# CW340_USERIO_SerialSelections.net
KiCad netlist of a schematic drawn in Altium Designer
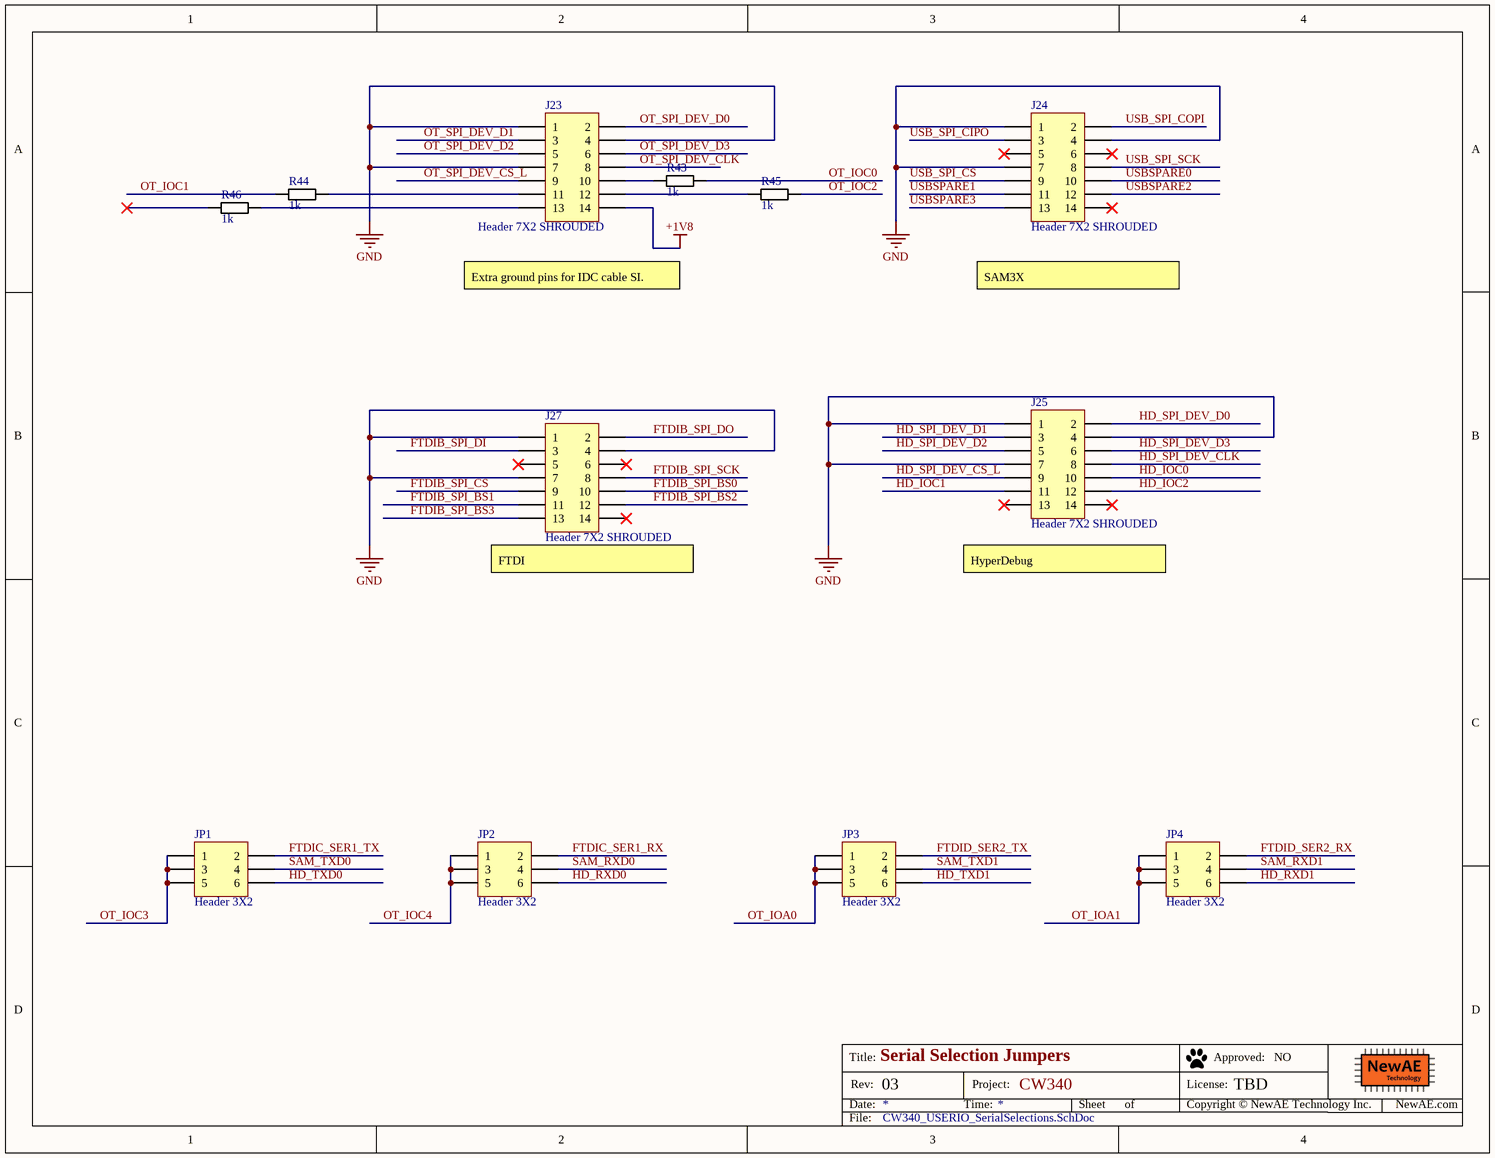
[diagram p0: CW340_USERIO_SerialSelections.SchDoc]

(export (version "E")
  (design (tool "Eeschema 10.0.6"))
  (components
    (comp (ref "J23")
      (value "Header 7X2 SHROUDED")
      (footprint "HDR2X7")
      (description "Header, 7-Pin, Dual row")
      (fields (field (name "PUBLISHER") "Altium Limited"))
      (libsource (lib "Miscellaneous Connectors") (part "Header 7X2"))
    )
    (comp (ref "J24")
      (value "Header 7X2 SHROUDED")
      (footprint "HDR2X7")
      (description "Header, 7-Pin, Dual row")
      (fields (field (name "PUBLISHER") "Altium Limited"))
      (libsource (lib "Miscellaneous Connectors") (part "Header 7X2"))
    )
    (comp (ref "J25")
      (value "Header 7X2 SHROUDED")
      (footprint "HDR2X7")
      (description "Header, 7-Pin, Dual row")
      (fields (field (name "PUBLISHER") "Altium Limited"))
      (libsource (lib "Miscellaneous Connectors") (part "Header 7X2"))
    )
    (comp (ref "J27")
      (value "Header 7X2 SHROUDED")
      (footprint "HDR2X7")
      (description "Header, 7-Pin, Dual row")
      (fields (field (name "PUBLISHER") "Altium Limited"))
      (libsource (lib "Miscellaneous Connectors") (part "Header 7X2"))
    )
    (comp (ref "JP1")
      (value "Header 3X2")
      (footprint "HDR2X3")
      (description "Header, 3-Pin, Dual row")
      (fields (field (name "PUBLISHER") "Altium Limited"))
      (libsource (lib "Miscellaneous Connectors") (part "Header 3X2"))
    )
    (comp (ref "JP2")
      (value "Header 3X2")
      (footprint "HDR2X3")
      (description "Header, 3-Pin, Dual row")
      (fields (field (name "PUBLISHER") "Altium Limited"))
      (libsource (lib "Miscellaneous Connectors") (part "Header 3X2"))
    )
    (comp (ref "JP3")
      (value "Header 3X2")
      (footprint "HDR2X3")
      (description "Header, 3-Pin, Dual row")
      (fields (field (name "PUBLISHER") "Altium Limited"))
      (libsource (lib "Miscellaneous Connectors") (part "Header 3X2"))
    )
    (comp (ref "JP4")
      (value "Header 3X2")
      (footprint "HDR2X3")
      (description "Header, 3-Pin, Dual row")
      (fields (field (name "PUBLISHER") "Altium Limited"))
      (libsource (lib "Miscellaneous Connectors") (part "Header 3X2"))
    )
    (comp (ref "R43")
      (value "1k")
      (footprint "RESC1608X55N")
      (description "1k res, 0603, 1%, 1/10W")
      (fields (field (name "PART NUMBER") "RCHIP-1K-0603") (field (name "TOLERANCE") "1%"))
      (libsource (lib "NewAE_AltiumLib") (part "RES-EU"))
    )
    (comp (ref "R44")
      (value "1k")
      (footprint "RESC1608X55N")
      (description "1k res, 0603, 1%, 1/10W")
      (fields (field (name "PART NUMBER") "RCHIP-1K-0603") (field (name "TOLERANCE") "1%"))
      (libsource (lib "NewAE_AltiumLib") (part "RES-EU"))
    )
    (comp (ref "R45")
      (value "1k")
      (footprint "RESC1608X55N")
      (description "1k res, 0603, 1%, 1/10W")
      (fields (field (name "PART NUMBER") "RCHIP-1K-0603") (field (name "TOLERANCE") "1%"))
      (libsource (lib "NewAE_AltiumLib") (part "RES-EU"))
    )
    (comp (ref "R46")
      (value "1k")
      (footprint "RESC1608X55N")
      (description "1k res, 0603, 1%, 1/10W")
      (fields (field (name "PART NUMBER") "RCHIP-1K-0603") (field (name "TOLERANCE") "1%"))
      (libsource (lib "NewAE_AltiumLib") (part "RES-EU"))
    )
  )
  (nets
    (net (code "1") (name "+1V8") (class "Default")
      (node (ref "J23") (pin "14") (pinfunction "14_14") (pintype "passive"))
    )
    (net (code "2") (name "/FTDIB_SPI_BS0") (class "Default")
      (node (ref "J27") (pin "10") (pinfunction "10_10") (pintype "passive"))
    )
    (net (code "3") (name "/FTDIB_SPI_BS1") (class "Default")
      (node (ref "J27") (pin "11") (pinfunction "11_11") (pintype "passive"))
    )
    (net (code "4") (name "/FTDIB_SPI_BS2") (class "Default")
      (node (ref "J27") (pin "12") (pinfunction "12_12") (pintype "passive"))
    )
    (net (code "5") (name "/FTDIB_SPI_BS3") (class "Default")
      (node (ref "J27") (pin "13") (pinfunction "13_13") (pintype "passive"))
    )
    (net (code "6") (name "/FTDIB_SPI_CS") (class "Default")
      (node (ref "J27") (pin "9") (pinfunction "9_9") (pintype "passive"))
    )
    (net (code "7") (name "/FTDIB_SPI_DI") (class "Default")
      (node (ref "J27") (pin "3") (pinfunction "3_3") (pintype "passive"))
    )
    (net (code "8") (name "/FTDIB_SPI_DO") (class "Default")
      (node (ref "J27") (pin "2") (pinfunction "2_2") (pintype "passive"))
    )
    (net (code "9") (name "/FTDIB_SPI_SCK") (class "Default")
      (node (ref "J27") (pin "8") (pinfunction "8_8") (pintype "passive"))
    )
    (net (code "10") (name "/FTDIC_SER1_RX") (class "Default")
      (node (ref "JP2") (pin "2") (pinfunction "2_2") (pintype "passive"))
    )
    (net (code "11") (name "/FTDIC_SER1_TX") (class "Default")
      (node (ref "JP1") (pin "2") (pinfunction "2_2") (pintype "passive"))
    )
    (net (code "12") (name "/FTDID_SER2_RX") (class "Default")
      (node (ref "JP4") (pin "2") (pinfunction "2_2") (pintype "passive"))
    )
    (net (code "13") (name "/FTDID_SER2_TX") (class "Default")
      (node (ref "JP3") (pin "2") (pinfunction "2_2") (pintype "passive"))
    )
    (net (code "14") (name "/HD_IOC0") (class "Default")
      (node (ref "J25") (pin "10") (pinfunction "10_10") (pintype "passive"))
    )
    (net (code "15") (name "/HD_IOC1") (class "Default")
      (node (ref "J25") (pin "11") (pinfunction "11_11") (pintype "passive"))
    )
    (net (code "16") (name "/HD_IOC2") (class "Default")
      (node (ref "J25") (pin "12") (pinfunction "12_12") (pintype "passive"))
    )
    (net (code "17") (name "/HD_RXD0") (class "Default")
      (node (ref "JP2") (pin "6") (pinfunction "6_6") (pintype "passive"))
    )
    (net (code "18") (name "/HD_RXD1") (class "Default")
      (node (ref "JP4") (pin "6") (pinfunction "6_6") (pintype "passive"))
    )
    (net (code "19") (name "/HD_SPI_DEV_CLK") (class "Default")
      (node (ref "J25") (pin "8") (pinfunction "8_8") (pintype "passive"))
    )
    (net (code "20") (name "/HD_SPI_DEV_CS_L") (class "Default")
      (node (ref "J25") (pin "9") (pinfunction "9_9") (pintype "passive"))
    )
    (net (code "21") (name "/HD_SPI_DEV_D0") (class "Default")
      (node (ref "J25") (pin "2") (pinfunction "2_2") (pintype "passive"))
    )
    (net (code "22") (name "/HD_SPI_DEV_D1") (class "Default")
      (node (ref "J25") (pin "3") (pinfunction "3_3") (pintype "passive"))
    )
    (net (code "23") (name "/HD_SPI_DEV_D2") (class "Default")
      (node (ref "J25") (pin "5") (pinfunction "5_5") (pintype "passive"))
    )
    (net (code "24") (name "/HD_SPI_DEV_D3") (class "Default")
      (node (ref "J25") (pin "6") (pinfunction "6_6") (pintype "passive"))
    )
    (net (code "25") (name "/HD_TXD0") (class "Default")
      (node (ref "JP1") (pin "6") (pinfunction "6_6") (pintype "passive"))
    )
    (net (code "26") (name "/HD_TXD1") (class "Default")
      (node (ref "JP3") (pin "6") (pinfunction "6_6") (pintype "passive"))
    )
    (net (code "27") (name "/OT_IOA0") (class "Default")
      (node (ref "JP3") (pin "1") (pinfunction "1_1") (pintype "passive"))
      (node (ref "JP3") (pin "3") (pinfunction "3_3") (pintype "passive"))
      (node (ref "JP3") (pin "5") (pinfunction "5_5") (pintype "passive"))
    )
    (net (code "28") (name "/OT_IOA1") (class "Default")
      (node (ref "JP4") (pin "1") (pinfunction "1_1") (pintype "passive"))
      (node (ref "JP4") (pin "3") (pinfunction "3_3") (pintype "passive"))
      (node (ref "JP4") (pin "5") (pinfunction "5_5") (pintype "passive"))
    )
    (net (code "29") (name "/OT_IOC0") (class "Default")
      (node (ref "R43") (pin "2") (pinfunction "2_2") (pintype "passive"))
    )
    (net (code "30") (name "/OT_IOC1") (class "Default")
      (node (ref "R44") (pin "1") (pinfunction "1_1") (pintype "passive"))
    )
    (net (code "31") (name "/OT_IOC2") (class "Default")
      (node (ref "R45") (pin "2") (pinfunction "2_2") (pintype "passive"))
    )
    (net (code "32") (name "/OT_IOC3") (class "Default")
      (node (ref "JP1") (pin "1") (pinfunction "1_1") (pintype "passive"))
      (node (ref "JP1") (pin "3") (pinfunction "3_3") (pintype "passive"))
      (node (ref "JP1") (pin "5") (pinfunction "5_5") (pintype "passive"))
    )
    (net (code "33") (name "/OT_IOC4") (class "Default")
      (node (ref "JP2") (pin "1") (pinfunction "1_1") (pintype "passive"))
      (node (ref "JP2") (pin "3") (pinfunction "3_3") (pintype "passive"))
      (node (ref "JP2") (pin "5") (pinfunction "5_5") (pintype "passive"))
    )
    (net (code "34") (name "/OT_SPI_DEV_CLK") (class "Default")
      (node (ref "J23") (pin "8") (pinfunction "8_8") (pintype "passive"))
    )
    (net (code "35") (name "/OT_SPI_DEV_CS_L") (class "Default")
      (node (ref "J23") (pin "9") (pinfunction "9_9") (pintype "passive"))
    )
    (net (code "36") (name "/OT_SPI_DEV_D0") (class "Default")
      (node (ref "J23") (pin "2") (pinfunction "2_2") (pintype "passive"))
    )
    (net (code "37") (name "/OT_SPI_DEV_D1") (class "Default")
      (node (ref "J23") (pin "3") (pinfunction "3_3") (pintype "passive"))
    )
    (net (code "38") (name "/OT_SPI_DEV_D2") (class "Default")
      (node (ref "J23") (pin "5") (pinfunction "5_5") (pintype "passive"))
    )
    (net (code "39") (name "/OT_SPI_DEV_D3") (class "Default")
      (node (ref "J23") (pin "6") (pinfunction "6_6") (pintype "passive"))
    )
    (net (code "40") (name "/SAM_RXD0") (class "Default")
      (node (ref "JP2") (pin "4") (pinfunction "4_4") (pintype "passive"))
    )
    (net (code "41") (name "/SAM_RXD1") (class "Default")
      (node (ref "JP4") (pin "4") (pinfunction "4_4") (pintype "passive"))
    )
    (net (code "42") (name "/SAM_TXD0") (class "Default")
      (node (ref "JP1") (pin "4") (pinfunction "4_4") (pintype "passive"))
    )
    (net (code "43") (name "/SAM_TXD1") (class "Default")
      (node (ref "JP3") (pin "4") (pinfunction "4_4") (pintype "passive"))
    )
    (net (code "44") (name "/USBSPARE0") (class "Default")
      (node (ref "J24") (pin "10") (pinfunction "10_10") (pintype "passive"))
    )
    (net (code "45") (name "/USBSPARE1") (class "Default")
      (node (ref "J24") (pin "11") (pinfunction "11_11") (pintype "passive"))
    )
    (net (code "46") (name "/USBSPARE2") (class "Default")
      (node (ref "J24") (pin "12") (pinfunction "12_12") (pintype "passive"))
    )
    (net (code "47") (name "/USBSPARE3") (class "Default")
      (node (ref "J24") (pin "13") (pinfunction "13_13") (pintype "passive"))
    )
    (net (code "48") (name "/USB_SPI_CIPO") (class "Default")
      (node (ref "J24") (pin "3") (pinfunction "3_3") (pintype "passive"))
    )
    (net (code "49") (name "/USB_SPI_COPI") (class "Default")
      (node (ref "J24") (pin "2") (pinfunction "2_2") (pintype "passive"))
    )
    (net (code "50") (name "/USB_SPI_CS") (class "Default")
      (node (ref "J24") (pin "9") (pinfunction "9_9") (pintype "passive"))
    )
    (net (code "51") (name "/USB_SPI_SCK") (class "Default")
      (node (ref "J24") (pin "8") (pinfunction "8_8") (pintype "passive"))
    )
    (net (code "52") (name "GND") (class "Default")
      (node (ref "J23") (pin "1") (pinfunction "1_1") (pintype "passive"))
      (node (ref "J23") (pin "4") (pinfunction "4_4") (pintype "passive"))
      (node (ref "J23") (pin "7") (pinfunction "7_7") (pintype "passive"))
      (node (ref "J24") (pin "1") (pinfunction "1_1") (pintype "passive"))
      (node (ref "J24") (pin "4") (pinfunction "4_4") (pintype "passive"))
      (node (ref "J24") (pin "7") (pinfunction "7_7") (pintype "passive"))
      (node (ref "J25") (pin "1") (pinfunction "1_1") (pintype "passive"))
      (node (ref "J25") (pin "4") (pinfunction "4_4") (pintype "passive"))
      (node (ref "J25") (pin "7") (pinfunction "7_7") (pintype "passive"))
      (node (ref "J27") (pin "1") (pinfunction "1_1") (pintype "passive"))
      (node (ref "J27") (pin "4") (pinfunction "4_4") (pintype "passive"))
      (node (ref "J27") (pin "7") (pinfunction "7_7") (pintype "passive"))
    )
    (net (code "53") (name "Net-(J23-Pad10)") (class "Default")
      (node (ref "J23") (pin "10") (pinfunction "10_10") (pintype "passive"))
      (node (ref "R43") (pin "1") (pinfunction "1_1") (pintype "passive"))
    )
    (net (code "54") (name "Net-(J23-Pad11)") (class "Default")
      (node (ref "J23") (pin "11") (pinfunction "11_11") (pintype "passive"))
      (node (ref "R44") (pin "2") (pinfunction "2_2") (pintype "passive"))
    )
    (net (code "55") (name "Net-(J23-Pad12)") (class "Default")
      (node (ref "J23") (pin "12") (pinfunction "12_12") (pintype "passive"))
      (node (ref "R45") (pin "1") (pinfunction "1_1") (pintype "passive"))
    )
    (net (code "56") (name "Net-(J23-Pad13)") (class "Default")
      (node (ref "J23") (pin "13") (pinfunction "13_13") (pintype "passive"))
      (node (ref "R46") (pin "2") (pinfunction "2_2") (pintype "passive"))
    )
    (net (code "57") (name "unconnected-(J24-Pad5)") (class "Default")
      (node (ref "J24") (pin "5") (pinfunction "5_5") (pintype "passive+no_connect"))
    )
    (net (code "58") (name "unconnected-(J24-Pad6)") (class "Default")
      (node (ref "J24") (pin "6") (pinfunction "6_6") (pintype "passive+no_connect"))
    )
    (net (code "59") (name "unconnected-(J24-Pad14)") (class "Default")
      (node (ref "J24") (pin "14") (pinfunction "14_14") (pintype "passive+no_connect"))
    )
    (net (code "60") (name "unconnected-(J25-Pad13)") (class "Default")
      (node (ref "J25") (pin "13") (pinfunction "13_13") (pintype "passive+no_connect"))
    )
    (net (code "61") (name "unconnected-(J25-Pad14)") (class "Default")
      (node (ref "J25") (pin "14") (pinfunction "14_14") (pintype "passive+no_connect"))
    )
    (net (code "62") (name "unconnected-(J27-Pad5)") (class "Default")
      (node (ref "J27") (pin "5") (pinfunction "5_5") (pintype "passive+no_connect"))
    )
    (net (code "63") (name "unconnected-(J27-Pad6)") (class "Default")
      (node (ref "J27") (pin "6") (pinfunction "6_6") (pintype "passive+no_connect"))
    )
    (net (code "64") (name "unconnected-(J27-Pad14)") (class "Default")
      (node (ref "J27") (pin "14") (pinfunction "14_14") (pintype "passive+no_connect"))
    )
    (net (code "65") (name "unconnected-(R46-Pad1)") (class "Default")
      (node (ref "R46") (pin "1") (pinfunction "1_1") (pintype "passive+no_connect"))
    )
  )
)
